# ESP8266_BREAKOUT.net
KiCad netlist of a schematic drawn in EAGLE
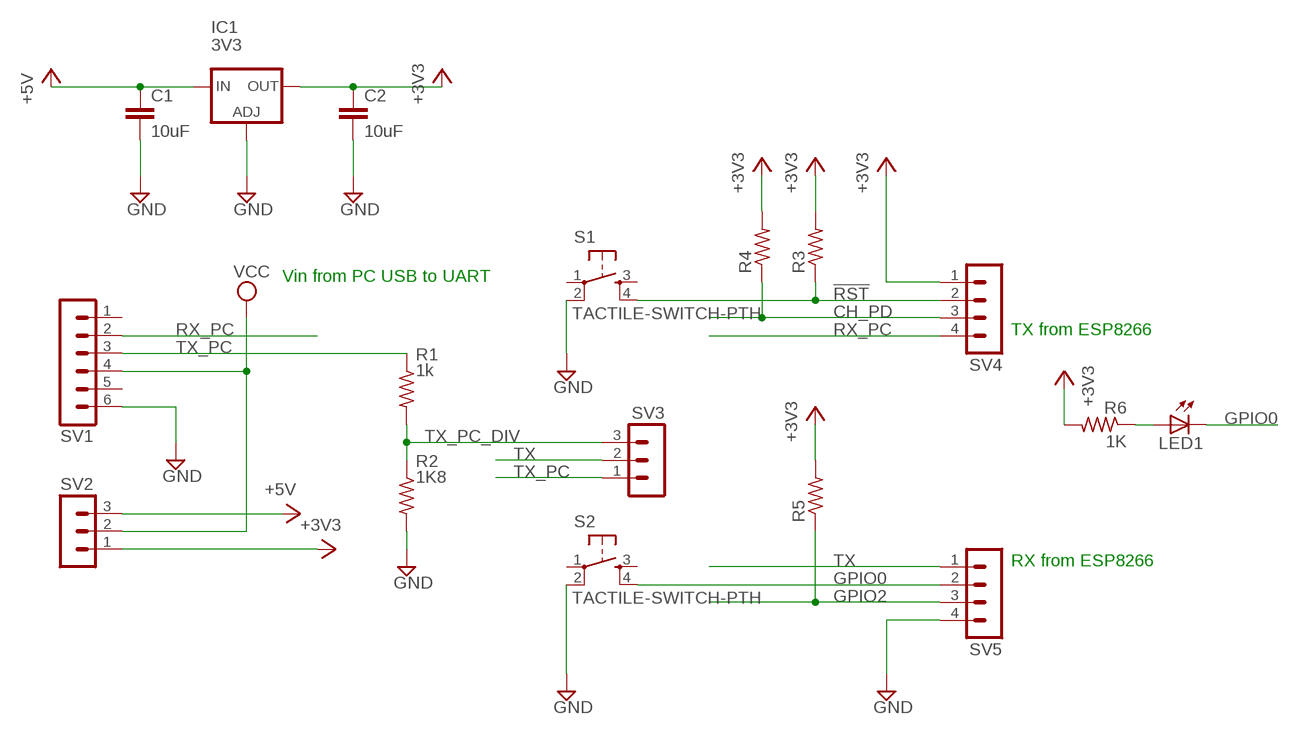
[diagram p0: schematic, sheet 1]

(export (version "E")
  (design (tool "Eeschema 10.0.6"))
  (components
    (comp (ref "C1")
      (value "10uF")
      (footprint "eagle-import:C5B2.5")
      (libsource (lib "eagle-import") (part "C5/2.5"))
    )
    (comp (ref "C2")
      (value "10uF")
      (footprint "eagle-import:C5B2.5")
      (libsource (lib "eagle-import") (part "C5/2.5"))
    )
    (comp (ref "IC1")
      (value "3V3")
      (footprint "eagle-import:317TS")
      (libsource (lib "eagle-import") (part "LM317TS"))
    )
    (comp (ref "LED1")
      (value "LED5MM")
      (footprint "eagle-import:LED5MM")
      (libsource (lib "eagle-import") (part "LED5MM"))
    )
    (comp (ref "R1")
      (value "1k")
      (footprint "eagle-import:0204_7")
      (libsource (lib "eagle-import") (part "R-US_0204/7"))
    )
    (comp (ref "R2")
      (value "1K8")
      (footprint "eagle-import:0204_7")
      (libsource (lib "eagle-import") (part "R-US_0204/7"))
    )
    (comp (ref "R3")
      (value "R-US_0204/7")
      (footprint "eagle-import:0204_7")
      (libsource (lib "eagle-import") (part "R-US_0204/7"))
    )
    (comp (ref "R4")
      (value "R-US_0204/7")
      (footprint "eagle-import:0204_7")
      (libsource (lib "eagle-import") (part "R-US_0204/7"))
    )
    (comp (ref "R5")
      (value "R-US_0204/7")
      (footprint "eagle-import:0204_7")
      (libsource (lib "eagle-import") (part "R-US_0204/7"))
    )
    (comp (ref "R6")
      (value "1K")
      (footprint "eagle-import:0204_7")
      (libsource (lib "eagle-import") (part "R-US_0204/7"))
    )
    (comp (ref "S1")
      (value "TACTILE-SWITCH-PTH")
      (footprint "eagle-import:TAC-SWITCH-PTH")
      (libsource (lib "eagle-import") (part "TACTILE-SWITCH-PTH"))
    )
    (comp (ref "S2")
      (value "TACTILE-SWITCH-PTH")
      (footprint "eagle-import:TAC-SWITCH-PTH")
      (libsource (lib "eagle-import") (part "TACTILE-SWITCH-PTH"))
    )
    (comp (ref "SV1")
      (value "MA06-1")
      (footprint "eagle-import:MA06-1")
      (libsource (lib "eagle-import") (part "MA06-1"))
    )
    (comp (ref "SV2")
      (value "MA03-1")
      (footprint "eagle-import:MA03-1")
      (libsource (lib "eagle-import") (part "MA03-1"))
    )
    (comp (ref "SV3")
      (value "MA03-1")
      (footprint "eagle-import:MA03-1")
      (libsource (lib "eagle-import") (part "MA03-1"))
    )
    (comp (ref "SV4")
      (value "MA04-1")
      (footprint "eagle-import:MA04-1")
      (libsource (lib "eagle-import") (part "MA04-1"))
    )
    (comp (ref "SV5")
      (value "MA04-1")
      (footprint "eagle-import:MA04-1")
      (libsource (lib "eagle-import") (part "MA04-1"))
    )
  )
  (nets
    (net (code "1") (name "+3V3") (class "Default")
      (node (ref "C2") (pin "1") (pinfunction "1_1") (pintype "passive"))
      (node (ref "IC1") (pin "2") (pinfunction "OUT_2") (pintype "passive"))
      (node (ref "R3") (pin "2") (pinfunction "2_2") (pintype "passive"))
      (node (ref "R4") (pin "2") (pinfunction "2_2") (pintype "passive"))
      (node (ref "R5") (pin "2") (pinfunction "2_2") (pintype "passive"))
      (node (ref "R6") (pin "2") (pinfunction "2_2") (pintype "passive"))
      (node (ref "SV2") (pin "1") (pinfunction "1_1") (pintype "passive"))
      (node (ref "SV4") (pin "1") (pinfunction "1_1") (pintype "passive"))
    )
    (net (code "2") (name "+5V") (class "Default")
      (node (ref "C1") (pin "1") (pinfunction "1_1") (pintype "passive"))
      (node (ref "IC1") (pin "3") (pinfunction "IN_3") (pintype "input"))
      (node (ref "SV2") (pin "3") (pinfunction "3_3") (pintype "passive"))
    )
    (net (code "3") (name "/CH_PD") (class "Default")
      (node (ref "R4") (pin "1") (pinfunction "1_1") (pintype "passive"))
      (node (ref "SV4") (pin "3") (pinfunction "3_3") (pintype "passive"))
    )
    (net (code "4") (name "/GPIO0") (class "Default")
      (node (ref "LED1") (pin "K") (pinfunction "C_K") (pintype "passive"))
      (node (ref "S2") (pin "4") (pinfunction "4_4") (pintype "passive"))
      (node (ref "SV5") (pin "2") (pinfunction "2_2") (pintype "passive"))
    )
    (net (code "5") (name "/GPIO2") (class "Default")
      (node (ref "R5") (pin "1") (pinfunction "1_1") (pintype "passive"))
      (node (ref "SV5") (pin "3") (pinfunction "3_3") (pintype "passive"))
    )
    (net (code "6") (name "/RX_PC") (class "Default")
      (node (ref "SV1") (pin "2") (pinfunction "2_2") (pintype "passive"))
      (node (ref "SV4") (pin "4") (pinfunction "4_4") (pintype "passive"))
    )
    (net (code "7") (name "/TX") (class "Default")
      (node (ref "SV3") (pin "2") (pinfunction "2_2") (pintype "passive"))
      (node (ref "SV5") (pin "1") (pinfunction "1_1") (pintype "passive"))
    )
    (net (code "8") (name "/TX_PC") (class "Default")
      (node (ref "R1") (pin "1") (pinfunction "1_1") (pintype "passive"))
      (node (ref "SV1") (pin "3") (pinfunction "3_3") (pintype "passive"))
      (node (ref "SV3") (pin "1") (pinfunction "1_1") (pintype "passive"))
    )
    (net (code "9") (name "/TX_PC_DIV") (class "Default")
      (node (ref "R1") (pin "2") (pinfunction "2_2") (pintype "passive"))
      (node (ref "R2") (pin "1") (pinfunction "1_1") (pintype "passive"))
      (node (ref "SV3") (pin "3") (pinfunction "3_3") (pintype "passive"))
    )
    (net (code "10") (name "/~{RST}") (class "Default")
      (node (ref "R3") (pin "1") (pinfunction "1_1") (pintype "passive"))
      (node (ref "S1") (pin "4") (pinfunction "4_4") (pintype "passive"))
      (node (ref "SV4") (pin "2") (pinfunction "2_2") (pintype "passive"))
    )
    (net (code "11") (name "GND") (class "Default")
      (node (ref "C1") (pin "2") (pinfunction "2_2") (pintype "passive"))
      (node (ref "C2") (pin "2") (pinfunction "2_2") (pintype "passive"))
      (node (ref "IC1") (pin "1") (pinfunction "ADJ_1") (pintype "input"))
      (node (ref "R2") (pin "2") (pinfunction "2_2") (pintype "passive"))
      (node (ref "S1") (pin "2") (pinfunction "2_2") (pintype "passive"))
      (node (ref "S2") (pin "2") (pinfunction "2_2") (pintype "passive"))
      (node (ref "SV1") (pin "6") (pinfunction "6_6") (pintype "passive"))
      (node (ref "SV5") (pin "4") (pinfunction "4_4") (pintype "passive"))
    )
    (net (code "12") (name "Net-(LED1-PadA)") (class "Default")
      (node (ref "LED1") (pin "A") (pinfunction "A_A") (pintype "passive"))
      (node (ref "R6") (pin "1") (pinfunction "1_1") (pintype "passive"))
    )
    (net (code "13") (name "VCC") (class "Default")
      (node (ref "SV1") (pin "4") (pinfunction "4_4") (pintype "passive"))
      (node (ref "SV2") (pin "2") (pinfunction "2_2") (pintype "passive"))
    )
    (net (code "14") (name "unconnected-(S1-Pad1)") (class "Default")
      (node (ref "S1") (pin "1") (pinfunction "1_1") (pintype "passive"))
    )
    (net (code "15") (name "unconnected-(S1-Pad3)") (class "Default")
      (node (ref "S1") (pin "3") (pinfunction "3_3") (pintype "passive"))
    )
    (net (code "16") (name "unconnected-(S2-Pad1)") (class "Default")
      (node (ref "S2") (pin "1") (pinfunction "1_1") (pintype "passive"))
    )
    (net (code "17") (name "unconnected-(S2-Pad3)") (class "Default")
      (node (ref "S2") (pin "3") (pinfunction "3_3") (pintype "passive"))
    )
    (net (code "18") (name "unconnected-(SV1-Pad1)") (class "Default")
      (node (ref "SV1") (pin "1") (pinfunction "1_1") (pintype "passive"))
    )
    (net (code "19") (name "unconnected-(SV1-Pad5)") (class "Default")
      (node (ref "SV1") (pin "5") (pinfunction "5_5") (pintype "passive"))
    )
  )
)
